# TLC591x-Interface-Board.net
KiCad netlist of a schematic drawn in EAGLE
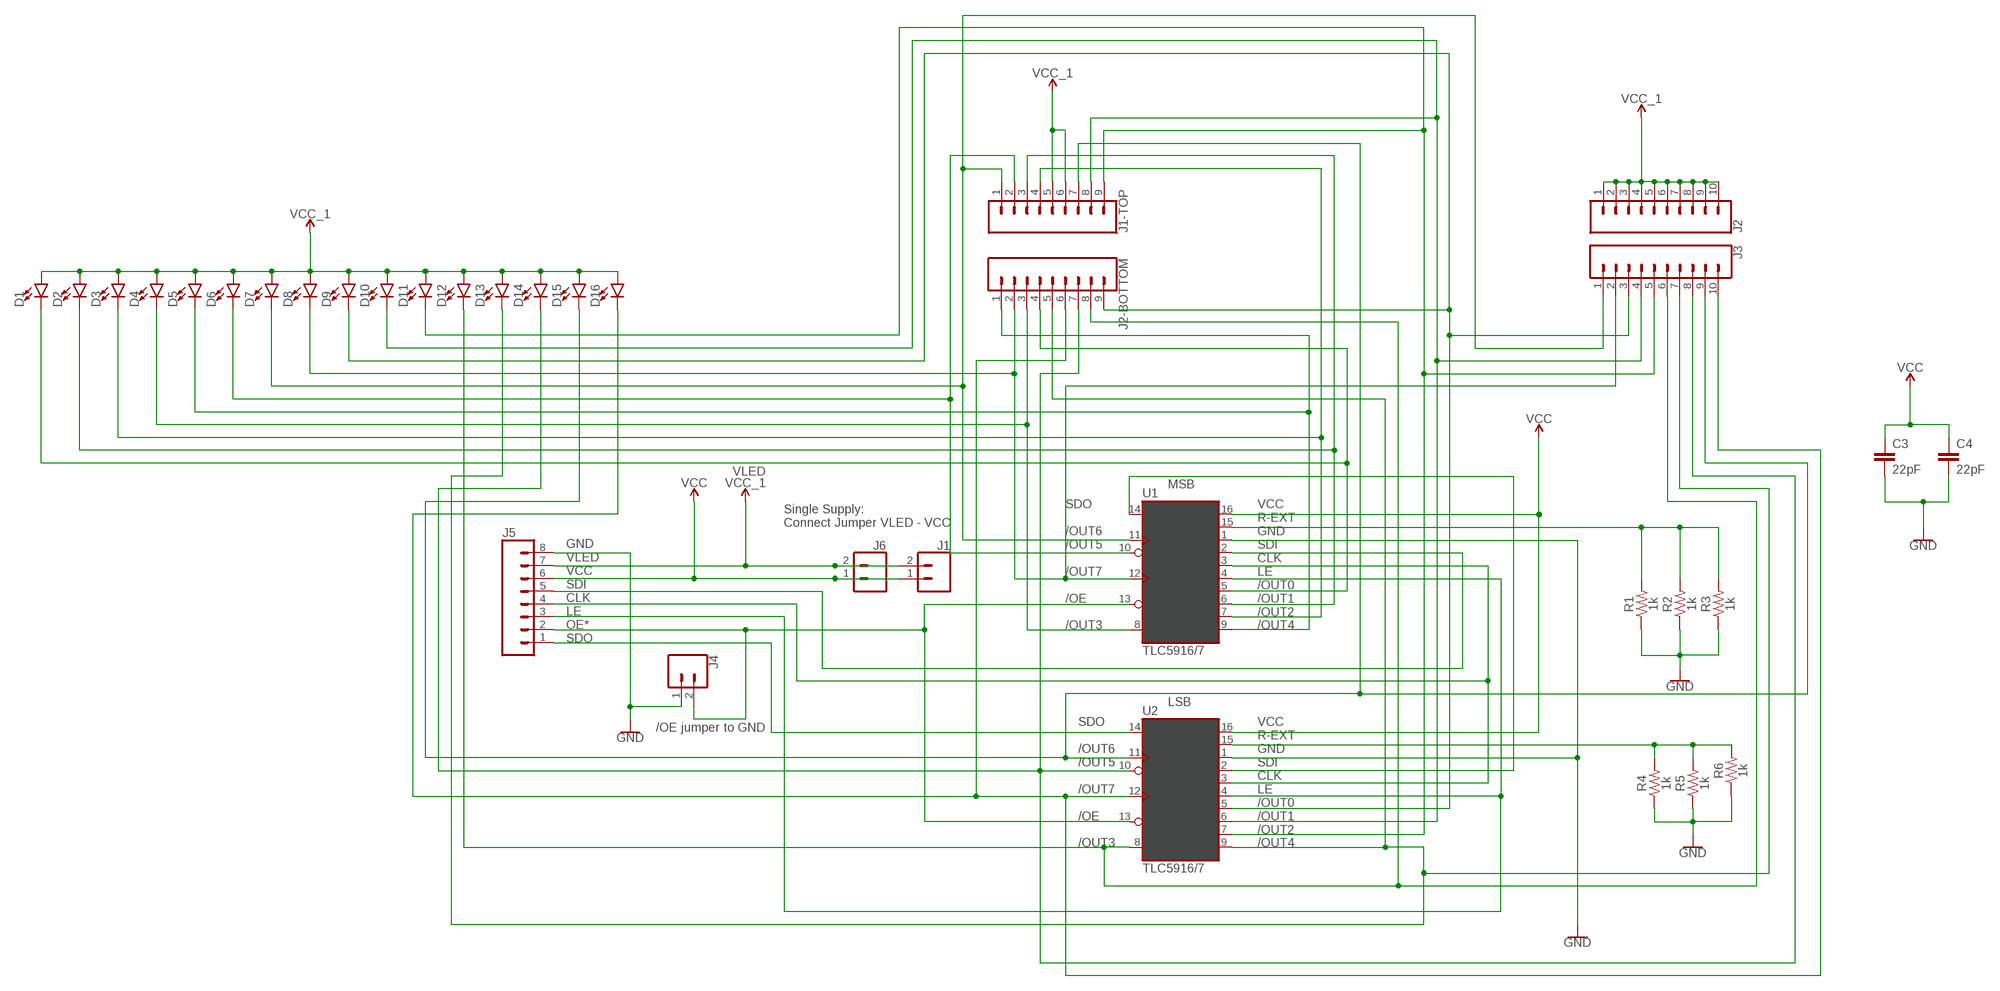
[diagram p0: schematic, sheet 1]

(export (version "E")
  (design (tool "Eeschema 10.0.6"))
  (components
    (comp (ref "C3")
      (value "22pF")
      (footprint "eagle-import:CAP-PTH-2.54")
      (libsource (lib "eagle-import") (part "22PF-PTH-2.54MM-200V-5%"))
    )
    (comp (ref "C4")
      (value "22pF")
      (footprint "eagle-import:CAP-PTH-2.54")
      (libsource (lib "eagle-import") (part "22PF-PTH-2.54MM-200V-5%"))
    )
    (comp (ref "D1")
      (value "LED3MM")
      (footprint "eagle-import:LED_3MM")
      (libsource (lib "eagle-import") (part "LED3MM"))
    )
    (comp (ref "D2")
      (value "LED3MM")
      (footprint "eagle-import:LED_3MM")
      (libsource (lib "eagle-import") (part "LED3MM"))
    )
    (comp (ref "D3")
      (value "LED3MM")
      (footprint "eagle-import:LED_3MM")
      (libsource (lib "eagle-import") (part "LED3MM"))
    )
    (comp (ref "D4")
      (value "LED3MM")
      (footprint "eagle-import:LED_3MM")
      (libsource (lib "eagle-import") (part "LED3MM"))
    )
    (comp (ref "D5")
      (value "LED3MM")
      (footprint "eagle-import:LED_3MM")
      (libsource (lib "eagle-import") (part "LED3MM"))
    )
    (comp (ref "D6")
      (value "LED3MM")
      (footprint "eagle-import:LED_3MM")
      (libsource (lib "eagle-import") (part "LED3MM"))
    )
    (comp (ref "D7")
      (value "LED3MM")
      (footprint "eagle-import:LED_3MM")
      (libsource (lib "eagle-import") (part "LED3MM"))
    )
    (comp (ref "D8")
      (value "LED3MM")
      (footprint "eagle-import:LED_3MM")
      (libsource (lib "eagle-import") (part "LED3MM"))
    )
    (comp (ref "D9")
      (value "LED3MM")
      (footprint "eagle-import:LED_3MM")
      (libsource (lib "eagle-import") (part "LED3MM"))
    )
    (comp (ref "D10")
      (value "LED3MM")
      (footprint "eagle-import:LED_3MM")
      (libsource (lib "eagle-import") (part "LED3MM"))
    )
    (comp (ref "D11")
      (value "LED3MM")
      (footprint "eagle-import:LED_3MM")
      (libsource (lib "eagle-import") (part "LED3MM"))
    )
    (comp (ref "D12")
      (value "LED3MM")
      (footprint "eagle-import:LED_3MM")
      (libsource (lib "eagle-import") (part "LED3MM"))
    )
    (comp (ref "D13")
      (value "LED3MM")
      (footprint "eagle-import:LED_3MM")
      (libsource (lib "eagle-import") (part "LED3MM"))
    )
    (comp (ref "D14")
      (value "LED3MM")
      (footprint "eagle-import:LED_3MM")
      (libsource (lib "eagle-import") (part "LED3MM"))
    )
    (comp (ref "D15")
      (value "LED3MM")
      (footprint "eagle-import:LED_3MM")
      (libsource (lib "eagle-import") (part "LED3MM"))
    )
    (comp (ref "D16")
      (value "LED3MM")
      (footprint "eagle-import:LED_3MM")
      (libsource (lib "eagle-import") (part "LED3MM"))
    )
    (comp (ref "J1")
      (value "CONN_02")
      (footprint "eagle-import:1X02")
      (libsource (lib "eagle-import") (part "CONN_02"))
    )
    (comp (ref "J1-TOP")
      (value "CONN_09")
      (footprint "eagle-import:1X09")
      (libsource (lib "eagle-import") (part "CONN_09"))
    )
    (comp (ref "J2")
      (value "CONN_10LOCK")
      (footprint "eagle-import:1X10_LOCK")
      (libsource (lib "eagle-import") (part "CONN_10LOCK"))
    )
    (comp (ref "J2-BOTTOM")
      (value "CONN_09")
      (footprint "eagle-import:1X09")
      (libsource (lib "eagle-import") (part "CONN_09"))
    )
    (comp (ref "J3")
      (value "CONN_10LOCK")
      (footprint "eagle-import:1X10_LOCK")
      (libsource (lib "eagle-import") (part "CONN_10LOCK"))
    )
    (comp (ref "J4")
      (value "CONN_02")
      (footprint "eagle-import:1X02")
      (libsource (lib "eagle-import") (part "CONN_02"))
    )
    (comp (ref "J5")
      (value "CONN_08LOCK")
      (footprint "eagle-import:1X08_LOCK")
      (libsource (lib "eagle-import") (part "CONN_08LOCK"))
    )
    (comp (ref "J6")
      (value "CONN_02")
      (footprint "eagle-import:1X02")
      (libsource (lib "eagle-import") (part "CONN_02"))
    )
    (comp (ref "R1")
      (value "1k")
      (footprint "eagle-import:AXIAL-0.3")
      (libsource (lib "eagle-import") (part "1KOHM-HORIZ-1/4W-1%"))
    )
    (comp (ref "R2")
      (value "1k")
      (footprint "eagle-import:AXIAL-0.3")
      (libsource (lib "eagle-import") (part "1KOHM-HORIZ-1/4W-1%"))
    )
    (comp (ref "R3")
      (value "1k")
      (footprint "eagle-import:AXIAL-0.3")
      (libsource (lib "eagle-import") (part "1KOHM-HORIZ-1/4W-1%"))
    )
    (comp (ref "R4")
      (value "1k")
      (footprint "eagle-import:AXIAL-0.3")
      (libsource (lib "eagle-import") (part "1KOHM-HORIZ-1/4W-1%"))
    )
    (comp (ref "R5")
      (value "1k")
      (footprint "eagle-import:AXIAL-0.3")
      (libsource (lib "eagle-import") (part "1KOHM-HORIZ-1/4W-1%"))
    )
    (comp (ref "R6")
      (value "1k")
      (footprint "eagle-import:AXIAL-0.3")
      (libsource (lib "eagle-import") (part "1KOHM-HORIZ-1/4W-1%"))
    )
    (comp (ref "U1")
      (value "TLC5916/7")
      (footprint "eagle-import:DIP16")
      (libsource (lib "eagle-import") (part "74595NHC"))
    )
    (comp (ref "U2")
      (value "TLC5916/7")
      (footprint "eagle-import:DIP16")
      (libsource (lib "eagle-import") (part "74595NHC"))
    )
  )
  (nets
    (net (code "1") (name "GND") (class "Default")
      (node (ref "C3") (pin "2") (pinfunction "2_2") (pintype "passive"))
      (node (ref "C4") (pin "2") (pinfunction "2_2") (pintype "passive"))
      (node (ref "J4") (pin "1") (pinfunction "1_1") (pintype "passive"))
      (node (ref "J5") (pin "8") (pinfunction "8_8") (pintype "passive"))
      (node (ref "R1") (pin "P$1") (pinfunction "1_P$1") (pintype "passive"))
      (node (ref "R2") (pin "P$1") (pinfunction "1_P$1") (pintype "passive"))
      (node (ref "R3") (pin "P$1") (pinfunction "1_P$1") (pintype "passive"))
      (node (ref "R4") (pin "P$1") (pinfunction "1_P$1") (pintype "passive"))
      (node (ref "R5") (pin "P$1") (pinfunction "1_P$1") (pintype "passive"))
      (node (ref "R6") (pin "P$1") (pinfunction "1_P$1") (pintype "passive"))
      (node (ref "U1") (pin "1") (pinfunction "QB_1") (pintype "tri_state"))
      (node (ref "U2") (pin "1") (pinfunction "QB_1") (pintype "tri_state"))
    )
    (net (code "2") (name "Net-(D1-C)") (class "Default")
      (node (ref "D1") (pin "K") (pinfunction "C_K") (pintype "passive"))
      (node (ref "J2-BOTTOM") (pin "4") (pinfunction "4_4") (pintype "passive"))
      (node (ref "U1") (pin "5") (pinfunction "QF_5") (pintype "tri_state"))
    )
    (net (code "3") (name "Net-(D2-C)") (class "Default")
      (node (ref "D2") (pin "K") (pinfunction "C_K") (pintype "passive"))
      (node (ref "J1-TOP") (pin "3") (pinfunction "3_3") (pintype "passive"))
      (node (ref "U1") (pin "6") (pinfunction "QG_6") (pintype "tri_state"))
    )
    (net (code "4") (name "Net-(D3-C)") (class "Default")
      (node (ref "D3") (pin "K") (pinfunction "C_K") (pintype "passive"))
      (node (ref "J1-TOP") (pin "4") (pinfunction "4_4") (pintype "passive"))
      (node (ref "U1") (pin "7") (pinfunction "QH_7") (pintype "tri_state"))
    )
    (net (code "5") (name "Net-(D4-C)") (class "Default")
      (node (ref "D4") (pin "K") (pinfunction "C_K") (pintype "passive"))
      (node (ref "J2-BOTTOM") (pin "3") (pinfunction "3_3") (pintype "passive"))
      (node (ref "U1") (pin "8") (pinfunction "GND_8") (pintype "power_in"))
    )
    (net (code "6") (name "Net-(D5-C)") (class "Default")
      (node (ref "D5") (pin "K") (pinfunction "C_K") (pintype "passive"))
      (node (ref "J2-BOTTOM") (pin "1") (pinfunction "1_1") (pintype "passive"))
      (node (ref "U1") (pin "9") (pinfunction "QH*_9") (pintype "tri_state"))
    )
    (net (code "7") (name "Net-(D6-C)") (class "Default")
      (node (ref "D6") (pin "K") (pinfunction "C_K") (pintype "passive"))
      (node (ref "J1-TOP") (pin "2") (pinfunction "2_2") (pintype "passive"))
      (node (ref "U1") (pin "10") (pinfunction "SCL_10") (pintype "input"))
    )
    (net (code "8") (name "Net-(D7-C)") (class "Default")
      (node (ref "D7") (pin "K") (pinfunction "C_K") (pintype "passive"))
      (node (ref "J1-TOP") (pin "1") (pinfunction "1_1") (pintype "passive"))
      (node (ref "J3") (pin "1") (pinfunction "1_1") (pintype "passive"))
      (node (ref "U1") (pin "11") (pinfunction "SCK_11") (pintype "input"))
    )
    (net (code "9") (name "Net-(D8-C)") (class "Default")
      (node (ref "D8") (pin "K") (pinfunction "C_K") (pintype "passive"))
      (node (ref "J2-BOTTOM") (pin "2") (pinfunction "2_2") (pintype "passive"))
      (node (ref "J3") (pin "2") (pinfunction "2_2") (pintype "passive"))
      (node (ref "U1") (pin "12") (pinfunction "RCK_12") (pintype "input"))
    )
    (net (code "10") (name "Net-(D9-C)") (class "Default")
      (node (ref "D9") (pin "K") (pinfunction "C_K") (pintype "passive"))
      (node (ref "J2-BOTTOM") (pin "9") (pinfunction "9_9") (pintype "passive"))
      (node (ref "J3") (pin "3") (pinfunction "3_3") (pintype "passive"))
      (node (ref "U2") (pin "5") (pinfunction "QF_5") (pintype "tri_state"))
    )
    (net (code "11") (name "Net-(D10-C)") (class "Default")
      (node (ref "D10") (pin "K") (pinfunction "C_K") (pintype "passive"))
      (node (ref "J1-TOP") (pin "8") (pinfunction "8_8") (pintype "passive"))
      (node (ref "J3") (pin "4") (pinfunction "4_4") (pintype "passive"))
      (node (ref "U2") (pin "6") (pinfunction "QG_6") (pintype "tri_state"))
    )
    (net (code "12") (name "Net-(D11-C)") (class "Default")
      (node (ref "D11") (pin "K") (pinfunction "C_K") (pintype "passive"))
      (node (ref "J1-TOP") (pin "9") (pinfunction "9_9") (pintype "passive"))
      (node (ref "J3") (pin "5") (pinfunction "5_5") (pintype "passive"))
      (node (ref "U2") (pin "7") (pinfunction "QH_7") (pintype "tri_state"))
    )
    (net (code "13") (name "Net-(D12-C)") (class "Default")
      (node (ref "D12") (pin "K") (pinfunction "C_K") (pintype "passive"))
      (node (ref "J2-BOTTOM") (pin "8") (pinfunction "8_8") (pintype "passive"))
      (node (ref "J3") (pin "6") (pinfunction "6_6") (pintype "passive"))
      (node (ref "U2") (pin "8") (pinfunction "GND_8") (pintype "power_in"))
    )
    (net (code "14") (name "Net-(D13-C)") (class "Default")
      (node (ref "D13") (pin "K") (pinfunction "C_K") (pintype "passive"))
      (node (ref "J2-BOTTOM") (pin "5") (pinfunction "5_5") (pintype "passive"))
      (node (ref "J3") (pin "7") (pinfunction "7_7") (pintype "passive"))
      (node (ref "U2") (pin "9") (pinfunction "QH*_9") (pintype "tri_state"))
    )
    (net (code "15") (name "Net-(D14-C)") (class "Default")
      (node (ref "D14") (pin "K") (pinfunction "C_K") (pintype "passive"))
      (node (ref "J2-BOTTOM") (pin "7") (pinfunction "7_7") (pintype "passive"))
      (node (ref "J3") (pin "8") (pinfunction "8_8") (pintype "passive"))
      (node (ref "U2") (pin "10") (pinfunction "SCL_10") (pintype "input"))
    )
    (net (code "16") (name "Net-(D15-C)") (class "Default")
      (node (ref "D15") (pin "K") (pinfunction "C_K") (pintype "passive"))
      (node (ref "J1-TOP") (pin "7") (pinfunction "7_7") (pintype "passive"))
      (node (ref "J3") (pin "9") (pinfunction "9_9") (pintype "passive"))
      (node (ref "U2") (pin "11") (pinfunction "SCK_11") (pintype "input"))
    )
    (net (code "17") (name "Net-(D16-C)") (class "Default")
      (node (ref "D16") (pin "K") (pinfunction "C_K") (pintype "passive"))
      (node (ref "J2-BOTTOM") (pin "6") (pinfunction "6_6") (pintype "passive"))
      (node (ref "J3") (pin "10") (pinfunction "10_10") (pintype "passive"))
      (node (ref "U2") (pin "12") (pinfunction "RCK_12") (pintype "input"))
    )
    (net (code "18") (name "Net-(R1-2)") (class "Default")
      (node (ref "R1") (pin "P$2") (pinfunction "2_P$2") (pintype "passive"))
      (node (ref "R2") (pin "P$2") (pinfunction "2_P$2") (pintype "passive"))
      (node (ref "R3") (pin "P$2") (pinfunction "2_P$2") (pintype "passive"))
      (node (ref "U1") (pin "15") (pinfunction "QA_15") (pintype "tri_state"))
    )
    (net (code "19") (name "Net-(R4-2)") (class "Default")
      (node (ref "R4") (pin "P$2") (pinfunction "2_P$2") (pintype "passive"))
      (node (ref "R5") (pin "P$2") (pinfunction "2_P$2") (pintype "passive"))
      (node (ref "R6") (pin "P$2") (pinfunction "2_P$2") (pintype "passive"))
      (node (ref "U2") (pin "15") (pinfunction "QA_15") (pintype "tri_state"))
    )
    (net (code "20") (name "Net-(U1-G)") (class "Default")
      (node (ref "J4") (pin "2") (pinfunction "2_2") (pintype "passive"))
      (node (ref "J5") (pin "2") (pinfunction "2_2") (pintype "passive"))
      (node (ref "U1") (pin "13") (pinfunction "G_13") (pintype "input"))
      (node (ref "U2") (pin "13") (pinfunction "G_13") (pintype "input"))
    )
    (net (code "21") (name "Net-(U1-QC)") (class "Default")
      (node (ref "J5") (pin "5") (pinfunction "5_5") (pintype "passive"))
      (node (ref "U1") (pin "2") (pinfunction "QC_2") (pintype "tri_state"))
    )
    (net (code "22") (name "Net-(U1-QD)") (class "Default")
      (node (ref "J5") (pin "4") (pinfunction "4_4") (pintype "passive"))
      (node (ref "U1") (pin "3") (pinfunction "QD_3") (pintype "tri_state"))
      (node (ref "U2") (pin "3") (pinfunction "QD_3") (pintype "tri_state"))
    )
    (net (code "23") (name "Net-(U1-QE)") (class "Default")
      (node (ref "J5") (pin "3") (pinfunction "3_3") (pintype "passive"))
      (node (ref "U1") (pin "4") (pinfunction "QE_4") (pintype "tri_state"))
      (node (ref "U2") (pin "4") (pinfunction "QE_4") (pintype "tri_state"))
    )
    (net (code "24") (name "Net-(U1-SER)") (class "Default")
      (node (ref "U1") (pin "14") (pinfunction "SER_14") (pintype "input"))
      (node (ref "U2") (pin "2") (pinfunction "QC_2") (pintype "tri_state"))
    )
    (net (code "25") (name "Net-(U2-SER)") (class "Default")
      (node (ref "J5") (pin "1") (pinfunction "1_1") (pintype "passive"))
      (node (ref "U2") (pin "14") (pinfunction "SER_14") (pintype "input"))
    )
    (net (code "26") (name "VCC") (class "Default")
      (node (ref "C3") (pin "1") (pinfunction "1_1") (pintype "passive"))
      (node (ref "C4") (pin "1") (pinfunction "1_1") (pintype "passive"))
      (node (ref "J1") (pin "1") (pinfunction "1_1") (pintype "passive"))
      (node (ref "J5") (pin "6") (pinfunction "6_6") (pintype "passive"))
      (node (ref "J6") (pin "1") (pinfunction "1_1") (pintype "passive"))
      (node (ref "U1") (pin "16") (pinfunction "VCC_16") (pintype "power_in"))
      (node (ref "U2") (pin "16") (pinfunction "VCC_16") (pintype "power_in"))
    )
    (net (code "27") (name "VCC_1") (class "Default")
      (node (ref "D1") (pin "A") (pinfunction "A_A") (pintype "passive"))
      (node (ref "D10") (pin "A") (pinfunction "A_A") (pintype "passive"))
      (node (ref "D11") (pin "A") (pinfunction "A_A") (pintype "passive"))
      (node (ref "D12") (pin "A") (pinfunction "A_A") (pintype "passive"))
      (node (ref "D13") (pin "A") (pinfunction "A_A") (pintype "passive"))
      (node (ref "D14") (pin "A") (pinfunction "A_A") (pintype "passive"))
      (node (ref "D15") (pin "A") (pinfunction "A_A") (pintype "passive"))
      (node (ref "D16") (pin "A") (pinfunction "A_A") (pintype "passive"))
      (node (ref "D2") (pin "A") (pinfunction "A_A") (pintype "passive"))
      (node (ref "D3") (pin "A") (pinfunction "A_A") (pintype "passive"))
      (node (ref "D4") (pin "A") (pinfunction "A_A") (pintype "passive"))
      (node (ref "D5") (pin "A") (pinfunction "A_A") (pintype "passive"))
      (node (ref "D6") (pin "A") (pinfunction "A_A") (pintype "passive"))
      (node (ref "D7") (pin "A") (pinfunction "A_A") (pintype "passive"))
      (node (ref "D8") (pin "A") (pinfunction "A_A") (pintype "passive"))
      (node (ref "D9") (pin "A") (pinfunction "A_A") (pintype "passive"))
      (node (ref "J1") (pin "2") (pinfunction "2_2") (pintype "passive"))
      (node (ref "J1-TOP") (pin "5") (pinfunction "5_5") (pintype "passive"))
      (node (ref "J1-TOP") (pin "6") (pinfunction "6_6") (pintype "passive"))
      (node (ref "J2") (pin "1") (pinfunction "1_1") (pintype "passive"))
      (node (ref "J2") (pin "10") (pinfunction "10_10") (pintype "passive"))
      (node (ref "J2") (pin "2") (pinfunction "2_2") (pintype "passive"))
      (node (ref "J2") (pin "3") (pinfunction "3_3") (pintype "passive"))
      (node (ref "J2") (pin "4") (pinfunction "4_4") (pintype "passive"))
      (node (ref "J2") (pin "5") (pinfunction "5_5") (pintype "passive"))
      (node (ref "J2") (pin "6") (pinfunction "6_6") (pintype "passive"))
      (node (ref "J2") (pin "7") (pinfunction "7_7") (pintype "passive"))
      (node (ref "J2") (pin "8") (pinfunction "8_8") (pintype "passive"))
      (node (ref "J2") (pin "9") (pinfunction "9_9") (pintype "passive"))
      (node (ref "J5") (pin "7") (pinfunction "7_7") (pintype "passive"))
      (node (ref "J6") (pin "2") (pinfunction "2_2") (pintype "passive"))
    )
  )
)
